# FinalSchematic.net
KiCad netlist of a schematic drawn in EAGLE
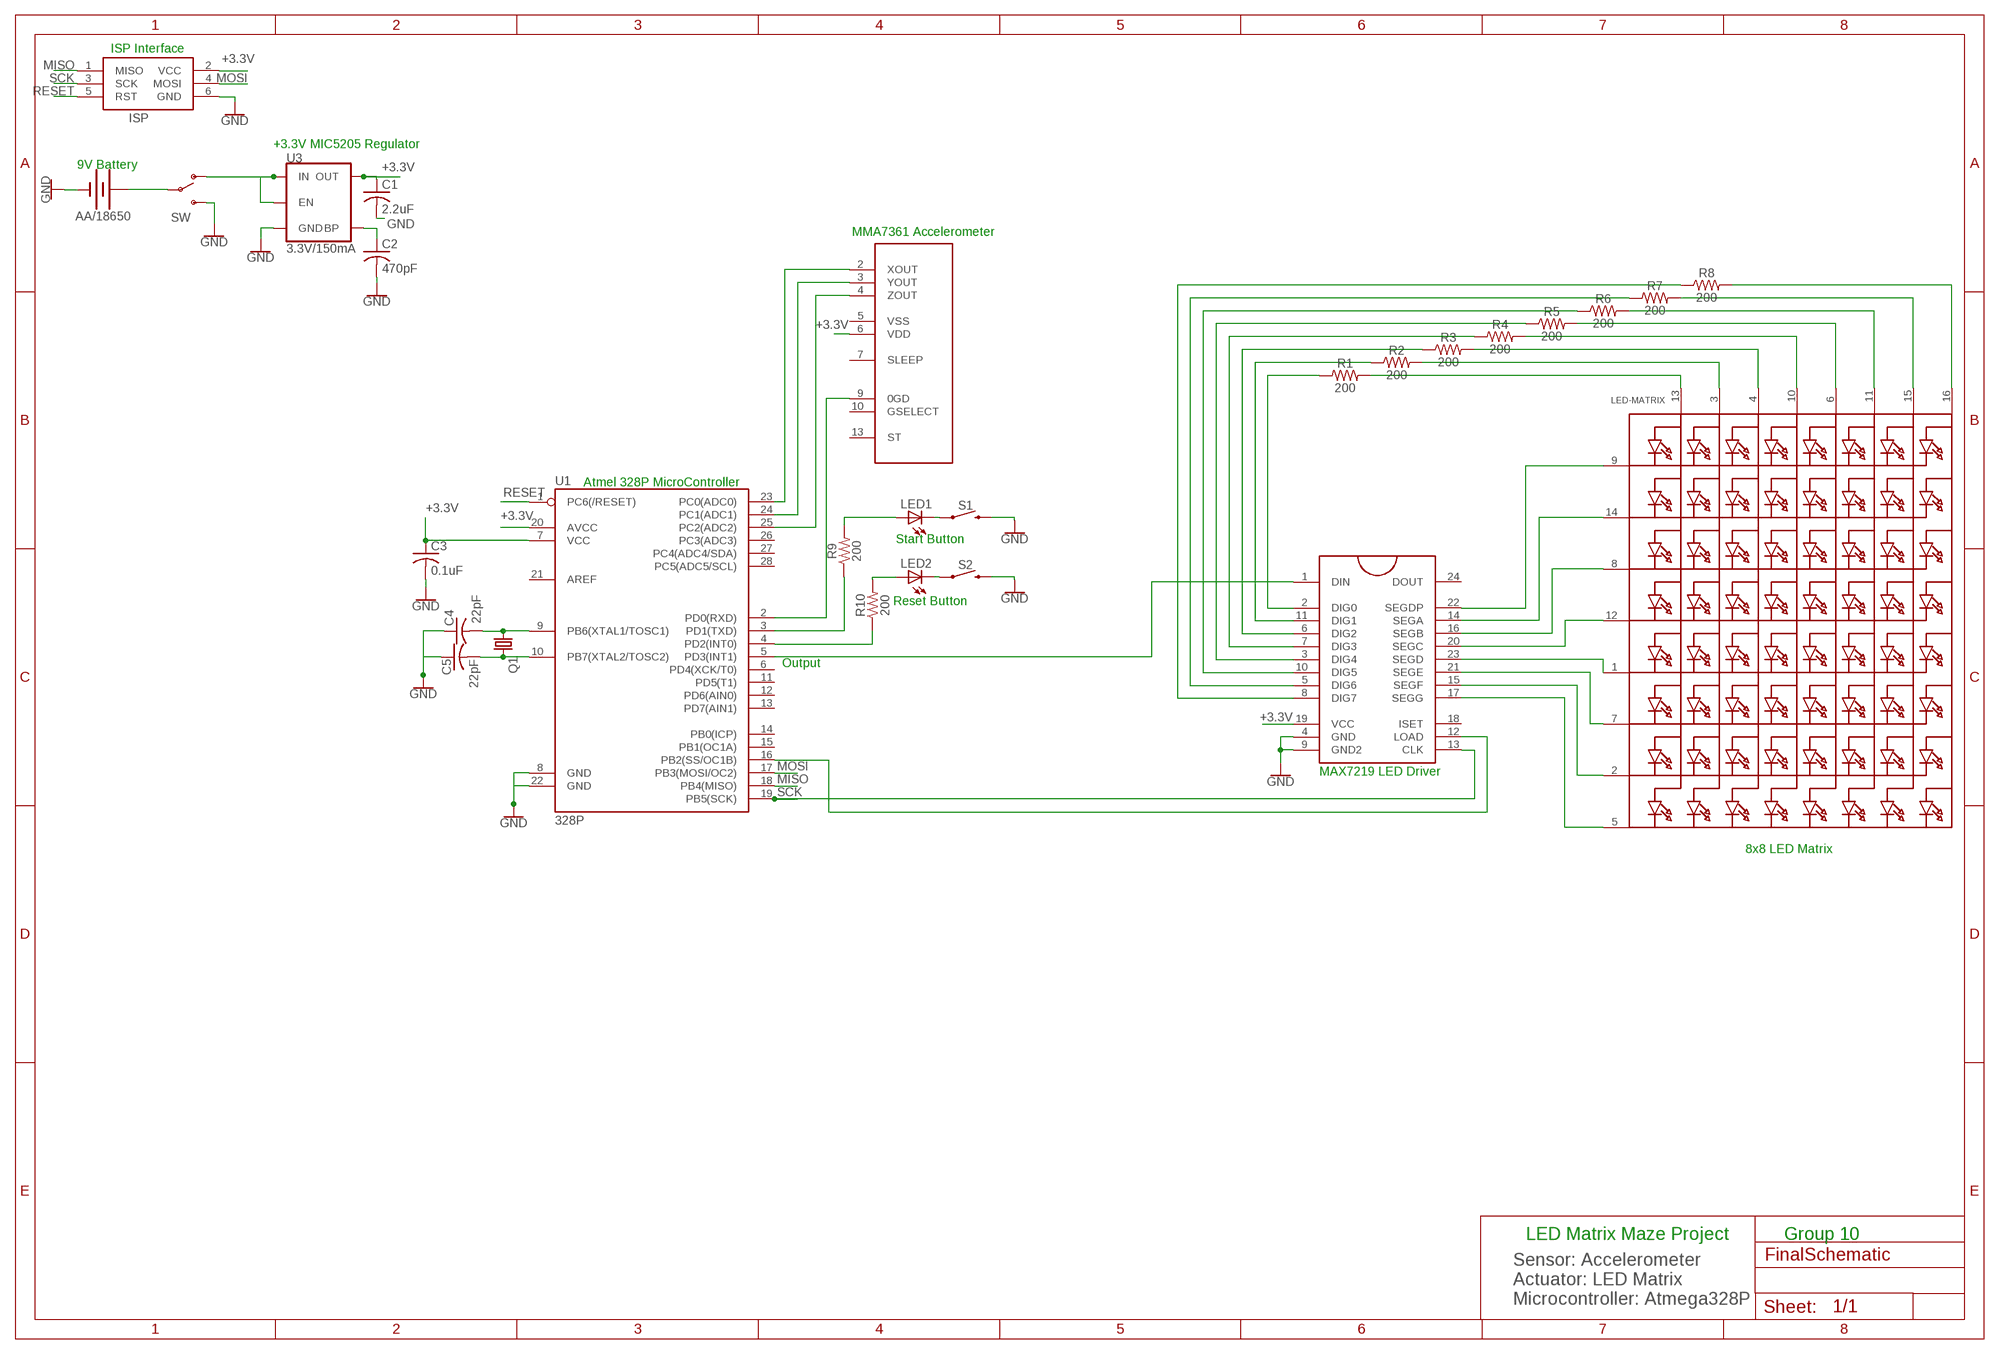
[diagram p0: schematic, sheet 1]

(export (version "E")
  (design (tool "Eeschema 10.0.6"))
  (components
    (comp (ref "AA/18650")
      (value "BATTERY-9V")
      (footprint "eagle-import:BATTCON_9V")
      (libsource (lib "eagle-import") (part "BATTERY-9V"))
    )
    (comp (ref "C1")
      (value "2.2uF")
      (footprint "eagle-import:C025-024X044")
      (libsource (lib "eagle-import") (part "C-US025-024X044"))
    )
    (comp (ref "C2")
      (value "470pF")
      (footprint "eagle-import:C025-024X044")
      (libsource (lib "eagle-import") (part "C-US025-024X044"))
    )
    (comp (ref "C3")
      (value "0.1uF")
      (footprint "eagle-import:C025-024X044")
      (libsource (lib "eagle-import") (part "C-US025-024X044"))
    )
    (comp (ref "C4")
      (value "22pF")
      (footprint "eagle-import:C025-024X044")
      (libsource (lib "eagle-import") (part "C-US025-024X044"))
    )
    (comp (ref "C5")
      (value "22pF")
      (footprint "eagle-import:C025-024X044")
      (libsource (lib "eagle-import") (part "C-US025-024X044"))
    )
    (comp (ref "ISP")
      (value "AVRISP-6")
      (footprint "eagle-import:AVRISP")
      (libsource (lib "eagle-import") (part "AVRISP-6"))
    )
    (comp (ref "LED-MATRIX")
      (value "SEGMENT_8X8_ROWCATHODEM12A881UR")
      (footprint "eagle-import:SEGMENT_BL-M12A881UR")
      (libsource (lib "eagle-import") (part "SEGMENT_8X8_ROWCATHODEM12A881UR"))
    )
    (comp (ref "LED1")
      (value "LED")
      (footprint "eagle-import:SMARTLED-TTW")
      (libsource (lib "eagle-import") (part "LED"))
    )
    (comp (ref "LED2")
      (value "LED")
      (footprint "eagle-import:SMARTLED-TTW")
      (libsource (lib "eagle-import") (part "LED"))
    )
    (comp (ref "Q1")
      (value "CRYSTALHC49S")
      (footprint "eagle-import:HC49_S")
      (libsource (lib "eagle-import") (part "CRYSTALHC49S"))
    )
    (comp (ref "R1")
      (value "200")
      (footprint "eagle-import:0603")
      (libsource (lib "eagle-import") (part "200OHM-0603-1/10W-1%"))
    )
    (comp (ref "R2")
      (value "200")
      (footprint "eagle-import:0603")
      (libsource (lib "eagle-import") (part "200OHM-0603-1/10W-1%"))
    )
    (comp (ref "R3")
      (value "200")
      (footprint "eagle-import:0603")
      (libsource (lib "eagle-import") (part "200OHM-0603-1/10W-1%"))
    )
    (comp (ref "R4")
      (value "200")
      (footprint "eagle-import:0603")
      (libsource (lib "eagle-import") (part "200OHM-0603-1/10W-1%"))
    )
    (comp (ref "R5")
      (value "200")
      (footprint "eagle-import:0603")
      (libsource (lib "eagle-import") (part "200OHM-0603-1/10W-1%"))
    )
    (comp (ref "R6")
      (value "200")
      (footprint "eagle-import:0603")
      (libsource (lib "eagle-import") (part "200OHM-0603-1/10W-1%"))
    )
    (comp (ref "R7")
      (value "200")
      (footprint "eagle-import:0603")
      (libsource (lib "eagle-import") (part "200OHM-0603-1/10W-1%"))
    )
    (comp (ref "R8")
      (value "200")
      (footprint "eagle-import:0603")
      (libsource (lib "eagle-import") (part "200OHM-0603-1/10W-1%"))
    )
    (comp (ref "R9")
      (value "200")
      (footprint "eagle-import:0603")
      (libsource (lib "eagle-import") (part "200OHM-0603-1/10W-1%"))
    )
    (comp (ref "R10")
      (value "200")
      (footprint "eagle-import:0603")
      (libsource (lib "eagle-import") (part "200OHM-0603-1/10W-1%"))
    )
    (comp (ref "S1")
      (value "MOMENTARY-SWITCH-SPST-SMD-6.0X3.5MM")
      (footprint "eagle-import:TACTILE_SWITCH_SMD_6.0X3.5MM")
      (libsource (lib "eagle-import") (part "MOMENTARY-SWITCH-SPST-SMD-6.0X3.5MM"))
    )
    (comp (ref "S2")
      (value "MOMENTARY-SWITCH-SPST-SMD-6.0X3.5MM")
      (footprint "eagle-import:TACTILE_SWITCH_SMD_6.0X3.5MM")
      (libsource (lib "eagle-import") (part "MOMENTARY-SWITCH-SPST-SMD-6.0X3.5MM"))
    )
    (comp (ref "SW")
      (value "SWITCH-SPSTPTH_LOCK")
      (footprint "eagle-import:SWITCH-SPDT_LOCK.007S")
      (libsource (lib "eagle-import") (part "SWITCH-SPSTPTH_LOCK"))
    )
    (comp (ref "U$1")
      (value "MAX7219DIP")
      (footprint "eagle-import:DIL24")
      (libsource (lib "eagle-import") (part "MAX7219DIP"))
    )
    (comp (ref "U$2")
      (value "MMA7361")
      (footprint "eagle-import:LGA14")
      (libsource (lib "eagle-import") (part "MMA7361"))
    )
    (comp (ref "U1")
      (value "328P")
      (footprint "eagle-import:DIP28")
      (libsource (lib "eagle-import") (part "ATMEGA328P_PDIP"))
    )
    (comp (ref "U3")
      (value "3.3V/150mA")
      (footprint "eagle-import:SOT23-5")
      (libsource (lib "eagle-import") (part "V_REG_MIC52053.3V"))
    )
  )
  (nets
    (net (code "1") (name "/+3.3V") (class "Default")
      (node (ref "C1") (pin "1") (pinfunction "1_1") (pintype "passive"))
      (node (ref "C3") (pin "1") (pinfunction "1_1") (pintype "passive"))
      (node (ref "ISP") (pin "2") (pinfunction "VCC_2") (pintype "power_in"))
      (node (ref "U$1") (pin "19") (pinfunction "VCC_19") (pintype "bidirectional"))
      (node (ref "U$2") (pin "6") (pinfunction "VDD_6") (pintype "bidirectional"))
      (node (ref "U1") (pin "20") (pinfunction "AVCC_20") (pintype "bidirectional"))
      (node (ref "U1") (pin "7") (pinfunction "VCC_7") (pintype "bidirectional"))
      (node (ref "U3") (pin "5") (pinfunction "OUT_5") (pintype "passive"))
    )
    (net (code "2") (name "/MISO") (class "Default")
      (node (ref "ISP") (pin "1") (pinfunction "MISO_1") (pintype "input"))
      (node (ref "U1") (pin "18") (pinfunction "PB4(MISO)_18") (pintype "bidirectional"))
    )
    (net (code "3") (name "/MOSI") (class "Default")
      (node (ref "ISP") (pin "4") (pinfunction "MOSI_4") (pintype "output"))
      (node (ref "U1") (pin "17") (pinfunction "PB3(MOSI/OC2)_17") (pintype "bidirectional"))
    )
    (net (code "4") (name "/RESET") (class "Default")
      (node (ref "ISP") (pin "5") (pinfunction "RST_5") (pintype "output"))
      (node (ref "U1") (pin "1") (pinfunction "PC6(/RESET)_1") (pintype "bidirectional"))
    )
    (net (code "5") (name "/SCK") (class "Default")
      (node (ref "ISP") (pin "3") (pinfunction "SCK_3") (pintype "output"))
      (node (ref "U$1") (pin "13") (pinfunction "CLK_13") (pintype "bidirectional"))
      (node (ref "U1") (pin "19") (pinfunction "PB5(SCK)_19") (pintype "bidirectional"))
    )
    (net (code "6") (name "GND") (class "Default")
      (node (ref "AA/18650") (pin "-") (pinfunction "-_-") (pintype "power_in"))
      (node (ref "C1") (pin "2") (pinfunction "2_2") (pintype "passive"))
      (node (ref "C2") (pin "2") (pinfunction "2_2") (pintype "passive"))
      (node (ref "C3") (pin "2") (pinfunction "2_2") (pintype "passive"))
      (node (ref "C4") (pin "1") (pinfunction "1_1") (pintype "passive"))
      (node (ref "C5") (pin "1") (pinfunction "1_1") (pintype "passive"))
      (node (ref "ISP") (pin "6") (pinfunction "GND_6") (pintype "power_in"))
      (node (ref "S1") (pin "2") (pinfunction "2_2") (pintype "passive"))
      (node (ref "S2") (pin "2") (pinfunction "2_2") (pintype "passive"))
      (node (ref "SW") (pin "3") (pinfunction "S_3") (pintype "passive"))
      (node (ref "U$1") (pin "4") (pinfunction "GND_4") (pintype "bidirectional"))
      (node (ref "U$1") (pin "9") (pinfunction "GND2_9") (pintype "bidirectional"))
      (node (ref "U1") (pin "22") (pinfunction "GND_22") (pintype "bidirectional"))
      (node (ref "U1") (pin "8") (pinfunction "GND_8") (pintype "bidirectional"))
      (node (ref "U3") (pin "2") (pinfunction "GND_2") (pintype "input"))
    )
    (net (code "7") (name "Net-(LED-MATRIX-A1)") (class "Default")
      (node (ref "LED-MATRIX") (pin "13") (pinfunction "A1_13") (pintype "bidirectional"))
      (node (ref "R1") (pin "2") (pinfunction "2_2") (pintype "passive"))
    )
    (net (code "8") (name "Net-(LED-MATRIX-A2)") (class "Default")
      (node (ref "LED-MATRIX") (pin "3") (pinfunction "A2_3") (pintype "bidirectional"))
      (node (ref "R2") (pin "2") (pinfunction "2_2") (pintype "passive"))
    )
    (net (code "9") (name "Net-(LED-MATRIX-A3)") (class "Default")
      (node (ref "LED-MATRIX") (pin "4") (pinfunction "A3_4") (pintype "bidirectional"))
      (node (ref "R3") (pin "2") (pinfunction "2_2") (pintype "passive"))
    )
    (net (code "10") (name "Net-(LED-MATRIX-A4)") (class "Default")
      (node (ref "LED-MATRIX") (pin "10") (pinfunction "A4_10") (pintype "bidirectional"))
      (node (ref "R4") (pin "2") (pinfunction "2_2") (pintype "passive"))
    )
    (net (code "11") (name "Net-(LED-MATRIX-A5)") (class "Default")
      (node (ref "LED-MATRIX") (pin "6") (pinfunction "A5_6") (pintype "bidirectional"))
      (node (ref "R5") (pin "2") (pinfunction "2_2") (pintype "passive"))
    )
    (net (code "12") (name "Net-(LED-MATRIX-A6)") (class "Default")
      (node (ref "LED-MATRIX") (pin "11") (pinfunction "A6_11") (pintype "bidirectional"))
      (node (ref "R6") (pin "2") (pinfunction "2_2") (pintype "passive"))
    )
    (net (code "13") (name "Net-(LED-MATRIX-A7)") (class "Default")
      (node (ref "LED-MATRIX") (pin "15") (pinfunction "A7_15") (pintype "bidirectional"))
      (node (ref "R7") (pin "2") (pinfunction "2_2") (pintype "passive"))
    )
    (net (code "14") (name "Net-(LED-MATRIX-A8)") (class "Default")
      (node (ref "LED-MATRIX") (pin "16") (pinfunction "A8_16") (pintype "bidirectional"))
      (node (ref "R8") (pin "2") (pinfunction "2_2") (pintype "passive"))
    )
    (net (code "15") (name "Net-(LED-MATRIX-K1)") (class "Default")
      (node (ref "LED-MATRIX") (pin "9") (pinfunction "K1_9") (pintype "bidirectional"))
      (node (ref "U$1") (pin "22") (pinfunction "SEGDP_22") (pintype "bidirectional"))
    )
    (net (code "16") (name "Net-(LED-MATRIX-K2)") (class "Default")
      (node (ref "LED-MATRIX") (pin "14") (pinfunction "K2_14") (pintype "bidirectional"))
      (node (ref "U$1") (pin "14") (pinfunction "SEGA_14") (pintype "bidirectional"))
    )
    (net (code "17") (name "Net-(LED-MATRIX-K3)") (class "Default")
      (node (ref "LED-MATRIX") (pin "8") (pinfunction "K3_8") (pintype "bidirectional"))
      (node (ref "U$1") (pin "16") (pinfunction "SEGB_16") (pintype "bidirectional"))
    )
    (net (code "18") (name "Net-(LED-MATRIX-K4)") (class "Default")
      (node (ref "LED-MATRIX") (pin "12") (pinfunction "K4_12") (pintype "bidirectional"))
      (node (ref "U$1") (pin "20") (pinfunction "SEGC_20") (pintype "bidirectional"))
    )
    (net (code "19") (name "Net-(LED-MATRIX-K5)") (class "Default")
      (node (ref "LED-MATRIX") (pin "1") (pinfunction "K5_1") (pintype "bidirectional"))
      (node (ref "U$1") (pin "23") (pinfunction "SEGD_23") (pintype "bidirectional"))
    )
    (net (code "20") (name "Net-(LED-MATRIX-K6)") (class "Default")
      (node (ref "LED-MATRIX") (pin "7") (pinfunction "K6_7") (pintype "bidirectional"))
      (node (ref "U$1") (pin "21") (pinfunction "SEGE_21") (pintype "bidirectional"))
    )
    (net (code "21") (name "Net-(LED-MATRIX-K7)") (class "Default")
      (node (ref "LED-MATRIX") (pin "2") (pinfunction "K7_2") (pintype "bidirectional"))
      (node (ref "U$1") (pin "15") (pinfunction "SEGF_15") (pintype "bidirectional"))
    )
    (net (code "22") (name "Net-(LED-MATRIX-K8)") (class "Default")
      (node (ref "LED-MATRIX") (pin "5") (pinfunction "K8_5") (pintype "bidirectional"))
      (node (ref "U$1") (pin "17") (pinfunction "SEGG_17") (pintype "bidirectional"))
    )
    (net (code "23") (name "Net-(LED1-A)") (class "Default")
      (node (ref "LED1") (pin "A@1") (pinfunction "A_A@1") (pintype "passive"))
      (node (ref "R9") (pin "2") (pinfunction "2_2") (pintype "passive"))
    )
    (net (code "24") (name "Net-(LED1-C)") (class "Default")
      (node (ref "LED1") (pin "C@1") (pinfunction "C_C@1") (pintype "passive"))
      (node (ref "S1") (pin "1") (pinfunction "1_1") (pintype "passive"))
    )
    (net (code "25") (name "Net-(LED2-A)") (class "Default")
      (node (ref "LED2") (pin "A@1") (pinfunction "A_A@1") (pintype "passive"))
      (node (ref "R10") (pin "2") (pinfunction "2_2") (pintype "passive"))
    )
    (net (code "26") (name "Net-(LED2-C)") (class "Default")
      (node (ref "LED2") (pin "C@1") (pinfunction "C_C@1") (pintype "passive"))
      (node (ref "S2") (pin "1") (pinfunction "1_1") (pintype "passive"))
    )
    (net (code "27") (name "Net-(SW-O)") (class "Default")
      (node (ref "SW") (pin "1") (pinfunction "O_1") (pintype "passive"))
      (node (ref "U3") (pin "1") (pinfunction "IN_1") (pintype "input"))
      (node (ref "U3") (pin "3") (pinfunction "EN_3") (pintype "input"))
    )
    (net (code "28") (name "Net-(SW-P)") (class "Default")
      (node (ref "AA/18650") (pin "+") (pinfunction "+_+") (pintype "power_in"))
      (node (ref "SW") (pin "2") (pinfunction "P_2") (pintype "passive"))
    )
    (net (code "29") (name "Net-(U$1-DIG0)") (class "Default")
      (node (ref "R1") (pin "1") (pinfunction "1_1") (pintype "passive"))
      (node (ref "U$1") (pin "2") (pinfunction "DIG0_2") (pintype "bidirectional"))
    )
    (net (code "30") (name "Net-(U$1-DIG1)") (class "Default")
      (node (ref "R2") (pin "1") (pinfunction "1_1") (pintype "passive"))
      (node (ref "U$1") (pin "11") (pinfunction "DIG1_11") (pintype "bidirectional"))
    )
    (net (code "31") (name "Net-(U$1-DIG2)") (class "Default")
      (node (ref "R3") (pin "1") (pinfunction "1_1") (pintype "passive"))
      (node (ref "U$1") (pin "6") (pinfunction "DIG2_6") (pintype "bidirectional"))
    )
    (net (code "32") (name "Net-(U$1-DIG3)") (class "Default")
      (node (ref "R4") (pin "1") (pinfunction "1_1") (pintype "passive"))
      (node (ref "U$1") (pin "7") (pinfunction "DIG3_7") (pintype "bidirectional"))
    )
    (net (code "33") (name "Net-(U$1-DIG4)") (class "Default")
      (node (ref "R5") (pin "1") (pinfunction "1_1") (pintype "passive"))
      (node (ref "U$1") (pin "3") (pinfunction "DIG4_3") (pintype "bidirectional"))
    )
    (net (code "34") (name "Net-(U$1-DIG5)") (class "Default")
      (node (ref "R6") (pin "1") (pinfunction "1_1") (pintype "passive"))
      (node (ref "U$1") (pin "10") (pinfunction "DIG5_10") (pintype "bidirectional"))
    )
    (net (code "35") (name "Net-(U$1-DIG6)") (class "Default")
      (node (ref "R7") (pin "1") (pinfunction "1_1") (pintype "passive"))
      (node (ref "U$1") (pin "5") (pinfunction "DIG6_5") (pintype "bidirectional"))
    )
    (net (code "36") (name "Net-(U$1-DIG7)") (class "Default")
      (node (ref "R8") (pin "1") (pinfunction "1_1") (pintype "passive"))
      (node (ref "U$1") (pin "8") (pinfunction "DIG7_8") (pintype "bidirectional"))
    )
    (net (code "37") (name "Net-(U$1-DIN)") (class "Default")
      (node (ref "U$1") (pin "1") (pinfunction "DIN_1") (pintype "bidirectional"))
      (node (ref "U1") (pin "5") (pinfunction "PD3(INT1)_5") (pintype "bidirectional"))
    )
    (net (code "38") (name "Net-(U$1-LOAD)") (class "Default")
      (node (ref "U$1") (pin "12") (pinfunction "LOAD_12") (pintype "bidirectional"))
      (node (ref "U1") (pin "16") (pinfunction "PB2(SS/OC1B)_16") (pintype "bidirectional"))
    )
    (net (code "39") (name "Net-(U$2-0GD)") (class "Default")
      (node (ref "U$2") (pin "9") (pinfunction "0GD_9") (pintype "bidirectional"))
      (node (ref "U1") (pin "2") (pinfunction "PD0(RXD)_2") (pintype "bidirectional"))
    )
    (net (code "40") (name "Net-(U$2-XOUT)") (class "Default")
      (node (ref "U$2") (pin "2") (pinfunction "XOUT_2") (pintype "bidirectional"))
      (node (ref "U1") (pin "23") (pinfunction "PC0(ADC0)_23") (pintype "bidirectional"))
    )
    (net (code "41") (name "Net-(U$2-YOUT)") (class "Default")
      (node (ref "U$2") (pin "3") (pinfunction "YOUT_3") (pintype "bidirectional"))
      (node (ref "U1") (pin "24") (pinfunction "PC1(ADC1)_24") (pintype "bidirectional"))
    )
    (net (code "42") (name "Net-(U$2-ZOUT)") (class "Default")
      (node (ref "U$2") (pin "4") (pinfunction "ZOUT_4") (pintype "bidirectional"))
      (node (ref "U1") (pin "25") (pinfunction "PC2(ADC2)_25") (pintype "bidirectional"))
    )
    (net (code "43") (name "Net-(U1-PB6(XTAL1{slash}TOSC1))") (class "Default")
      (node (ref "C4") (pin "2") (pinfunction "2_2") (pintype "passive"))
      (node (ref "Q1") (pin "1") (pinfunction "1_1") (pintype "passive"))
      (node (ref "U1") (pin "9") (pinfunction "PB6(XTAL1/TOSC1)_9") (pintype "bidirectional"))
    )
    (net (code "44") (name "Net-(U1-PB7(XTAL2{slash}TOSC2))") (class "Default")
      (node (ref "C5") (pin "2") (pinfunction "2_2") (pintype "passive"))
      (node (ref "Q1") (pin "2") (pinfunction "2_2") (pintype "passive"))
      (node (ref "U1") (pin "10") (pinfunction "PB7(XTAL2/TOSC2)_10") (pintype "bidirectional"))
    )
    (net (code "45") (name "Net-(U1-PD1(TXD))") (class "Default")
      (node (ref "R9") (pin "1") (pinfunction "1_1") (pintype "passive"))
      (node (ref "U1") (pin "3") (pinfunction "PD1(TXD)_3") (pintype "bidirectional"))
    )
    (net (code "46") (name "Net-(U1-PD2(INT0))") (class "Default")
      (node (ref "R10") (pin "1") (pinfunction "1_1") (pintype "passive"))
      (node (ref "U1") (pin "4") (pinfunction "PD2(INT0)_4") (pintype "bidirectional"))
    )
    (net (code "47") (name "Net-(U3-BP)") (class "Default")
      (node (ref "C2") (pin "1") (pinfunction "1_1") (pintype "passive"))
      (node (ref "U3") (pin "4") (pinfunction "BP_4") (pintype "input"))
    )
    (net (code "48") (name "unconnected-(U$1-DOUT-Pad24)") (class "Default")
      (node (ref "U$1") (pin "24") (pinfunction "DOUT_24") (pintype "bidirectional"))
    )
    (net (code "49") (name "unconnected-(U$1-ISET-Pad18)") (class "Default")
      (node (ref "U$1") (pin "18") (pinfunction "ISET_18") (pintype "bidirectional"))
    )
    (net (code "50") (name "unconnected-(U$2-GSELECT-Pad10)") (class "Default")
      (node (ref "U$2") (pin "10") (pinfunction "GSELECT_10") (pintype "bidirectional"))
    )
    (net (code "51") (name "unconnected-(U$2-SLEEP-Pad7)") (class "Default")
      (node (ref "U$2") (pin "7") (pinfunction "SLEEP_7") (pintype "bidirectional"))
    )
    (net (code "52") (name "unconnected-(U$2-ST-Pad13)") (class "Default")
      (node (ref "U$2") (pin "13") (pinfunction "ST_13") (pintype "bidirectional"))
    )
    (net (code "53") (name "unconnected-(U$2-VSS-Pad5)") (class "Default")
      (node (ref "U$2") (pin "5") (pinfunction "VSS_5") (pintype "bidirectional"))
    )
    (net (code "54") (name "unconnected-(U1-AREF-Pad21)") (class "Default")
      (node (ref "U1") (pin "21") (pinfunction "AREF_21") (pintype "bidirectional"))
    )
    (net (code "55") (name "unconnected-(U1-PB0(ICP)-Pad14)") (class "Default")
      (node (ref "U1") (pin "14") (pinfunction "PB0(ICP)_14") (pintype "bidirectional"))
    )
    (net (code "56") (name "unconnected-(U1-PB1(OC1A)-Pad15)") (class "Default")
      (node (ref "U1") (pin "15") (pinfunction "PB1(OC1A)_15") (pintype "bidirectional"))
    )
    (net (code "57") (name "unconnected-(U1-PC3(ADC3)-Pad26)") (class "Default")
      (node (ref "U1") (pin "26") (pinfunction "PC3(ADC3)_26") (pintype "bidirectional"))
    )
    (net (code "58") (name "unconnected-(U1-PC4(ADC4{slash}SDA)-Pad27)") (class "Default")
      (node (ref "U1") (pin "27") (pinfunction "PC4(ADC4/SDA)_27") (pintype "bidirectional"))
    )
    (net (code "59") (name "unconnected-(U1-PC5(ADC5{slash}SCL)-Pad28)") (class "Default")
      (node (ref "U1") (pin "28") (pinfunction "PC5(ADC5/SCL)_28") (pintype "bidirectional"))
    )
    (net (code "60") (name "unconnected-(U1-PD4(XCK{slash}T0)-Pad6)") (class "Default")
      (node (ref "U1") (pin "6") (pinfunction "PD4(XCK/T0)_6") (pintype "bidirectional"))
    )
    (net (code "61") (name "unconnected-(U1-PD5(T1)-Pad11)") (class "Default")
      (node (ref "U1") (pin "11") (pinfunction "PD5(T1)_11") (pintype "bidirectional"))
    )
    (net (code "62") (name "unconnected-(U1-PD6(AIN0)-Pad12)") (class "Default")
      (node (ref "U1") (pin "12") (pinfunction "PD6(AIN0)_12") (pintype "bidirectional"))
    )
    (net (code "63") (name "unconnected-(U1-PD7(AIN1)-Pad13)") (class "Default")
      (node (ref "U1") (pin "13") (pinfunction "PD7(AIN1)_13") (pintype "bidirectional"))
    )
  )
)
